# bumper.net
KiCad netlist of a schematic drawn in Altium Designer
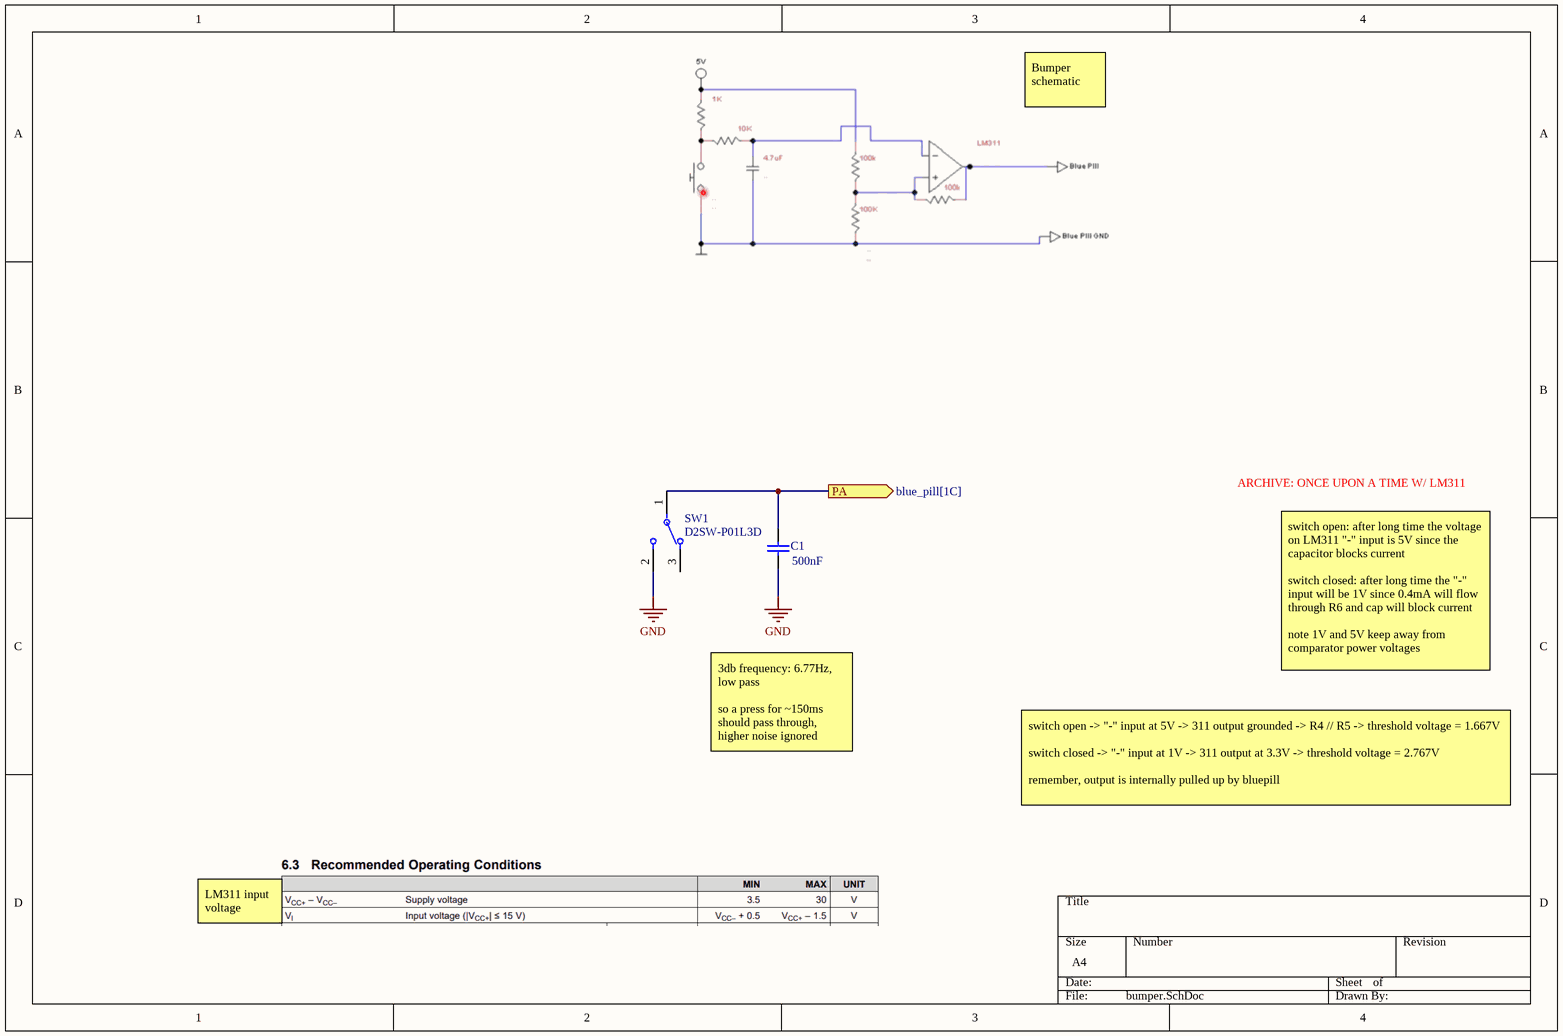
[diagram p0: bumper.SchDoc]

(export (version "E")
  (design (tool "Eeschema 10.0.6"))
  (components
    (comp (ref "C1")
      (value "500nF")
      (description "Capacitor")
      (libsource (lib "Simulation Generic Components") (part "Capacitor"))
    )
    (comp (ref "SW1")
      (value "D2SW-P01L3D")
      (footprint "FP-D2SW-P01L3D-MFG")
      (description "SWITCH SNAP ACT SPDT 100MA 125V")
      (libsource (lib "Altium Content Vault") (part "7ab140c03aa1c68131fe7f235f220d2"))
    )
  )
  (nets
    (net (code "1") (name "/PA") (class "Default")
      (node (ref "C1") (pin "1") (pinfunction "1_1") (pintype "passive"))
      (node (ref "SW1") (pin "1") (pinfunction "COM_1") (pintype "passive"))
    )
    (net (code "2") (name "GND") (class "Default")
      (node (ref "C1") (pin "2") (pinfunction "2_2") (pintype "passive"))
      (node (ref "SW1") (pin "2") (pinfunction "NO_2") (pintype "passive"))
    )
    (net (code "3") (name "unconnected-(SW1-NC-Pad3)") (class "Default")
      (node (ref "SW1") (pin "3") (pinfunction "NC_3") (pintype "passive"))
    )
  )
)
